# LED_PCB_3SMD.net
KiCad netlist of a schematic drawn in EAGLE
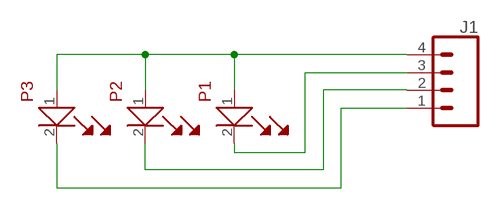
[diagram p0: schematic, sheet 1]

(export (version "E")
  (design (tool "Eeschema 10.0.6"))
  (components
    (comp (ref "J1")
      (value "CONN_04LONGPADS")
      (footprint "eagle-import:1X04_LONGPADS")
      (libsource (lib "eagle-import") (part "CONN_04LONGPADS"))
    )
    (comp (ref "P1")
      (value "OSRAM-LED")
      (footprint "eagle-import:SMD-2")
      (libsource (lib "eagle-import") (part "OSRAM-LED"))
    )
    (comp (ref "P2")
      (value "OSRAM-LED")
      (footprint "eagle-import:SMD-2")
      (libsource (lib "eagle-import") (part "OSRAM-LED"))
    )
    (comp (ref "P3")
      (value "OSRAM-LED")
      (footprint "eagle-import:SMD-2")
      (libsource (lib "eagle-import") (part "OSRAM-LED"))
    )
  )
  (nets
    (net (code "1") (name "Net-(P1-ANODE)") (class "Default")
      (node (ref "J1") (pin "4") (pinfunction "4_4") (pintype "passive"))
      (node (ref "P1") (pin "1") (pinfunction "ANODE_1") (pintype "input"))
      (node (ref "P2") (pin "1") (pinfunction "ANODE_1") (pintype "input"))
      (node (ref "P3") (pin "1") (pinfunction "ANODE_1") (pintype "input"))
    )
    (net (code "2") (name "Net-(P1-CATHODE)") (class "Default")
      (node (ref "J1") (pin "3") (pinfunction "3_3") (pintype "passive"))
      (node (ref "P1") (pin "2") (pinfunction "CATHODE_2") (pintype "output"))
    )
    (net (code "3") (name "Net-(P2-CATHODE)") (class "Default")
      (node (ref "J1") (pin "2") (pinfunction "2_2") (pintype "passive"))
      (node (ref "P2") (pin "2") (pinfunction "CATHODE_2") (pintype "output"))
    )
    (net (code "4") (name "Net-(P3-CATHODE)") (class "Default")
      (node (ref "J1") (pin "1") (pinfunction "1_1") (pintype "passive"))
      (node (ref "P3") (pin "2") (pinfunction "CATHODE_2") (pintype "output"))
    )
  )
)
